# Half_Bridge.net
KiCad netlist of a schematic drawn in Altium Designer
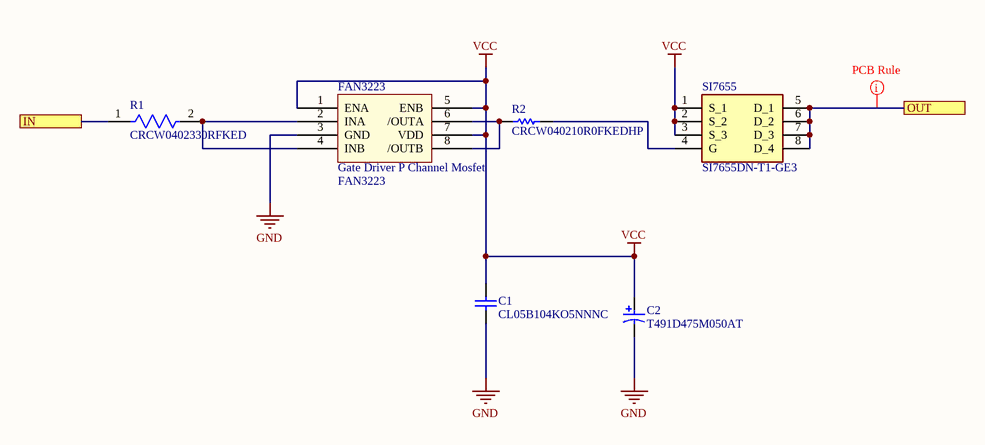
[diagram p0: Half_Bridge.SchDoc]

(export (version "E")
  (design (tool "Eeschema 10.0.6"))
  (components
    (comp (ref "C1")
      (value "CL05B104KO5NNNC")
      (footprint "CAPC1050X55X23ML05T13")
      (description "Chip Capacitor, 100 nF, +/- 10%, 16 V, -55 to 125 degC, 0402 (1005 Metric), RoHS, Tape and Reel")
      (fields (field (name "MANUFACTURER") "Samsung Electro-Mechanics"))
      (libsource (lib "Altium Content Vault") (part "CAP-NP-2"))
    )
    (comp (ref "C2")
      (value "T491D475M050AT")
      (footprint "KEMT-T491-D_L")
      (fields (field (name "VOLTAGE") "50VDC") (field (name "MANUFACTURER") "Kemet"))
      (libsource (lib "Altium Content Vault") (part "CAP-P-2"))
    )
    (comp (ref "FAN3223")
      (value "Gate Driver P Channel Mosfet")
      (footprint "FAN3223")
      (fields (field (name "ALTIUM_VALUE") "FAN3223"))
      (libsource (lib "FAN3223CMX") (part "FAN3223"))
    )
    (comp (ref "R1")
      (value "CRCW0402330RFKED")
      (footprint "FP-CRCW0402-e3-MFG")
      (description "RES Thick Film, 330Ω, 1%, 0.063W, 100ppm/°C, 0402")
      (fields (field (name "TOLERANCE") "1%"))
      (libsource (lib "Altium Content Vault") (part "1029c3af85768c4190bb7ad29bc67b5"))
    )
    (comp (ref "R2")
      (value "CRCW040210R0FKEDHP")
      (footprint "RESC1005X40X25NL05T10")
      (fields (field (name "MANUFACTURER") "Vishay Dale"))
      (libsource (lib "Altium Content Vault") (part "RES"))
    )
    (comp (ref "SI7655")
      (value "SI7655DN-T1-GE3")
      (footprint "SamacSys:SIS862DNT1GE3")
      (description "MOSFET (P-Channel)")
      (fields (field (name "MOUSER PART NUMBER") "78-SI7655DN-T1-GE3"))
      (libsource (lib "*") (part "SI7655DN-T1-GE3"))
    )
  )
  (nets
    (net (code "1") (name "/IN") (class "Default")
      (node (ref "R1") (pin "1") (pinfunction "1_1") (pintype "passive"))
    )
    (net (code "2") (name "/OUT") (class "Default")
      (node (ref "SI7655") (pin "5") (pinfunction "D_1_5") (pintype "passive"))
      (node (ref "SI7655") (pin "6") (pinfunction "D_2_6") (pintype "passive"))
      (node (ref "SI7655") (pin "7") (pinfunction "D_3_7") (pintype "passive"))
      (node (ref "SI7655") (pin "8") (pinfunction "D_4_8") (pintype "passive"))
    )
    (net (code "3") (name "GND") (class "Default")
      (node (ref "C1") (pin "1") (pinfunction "1_1") (pintype "passive"))
      (node (ref "C2") (pin "2") (pinfunction "2_2") (pintype "passive"))
      (node (ref "FAN3223") (pin "3") (pinfunction "GND_3") (pintype "passive"))
    )
    (net (code "4") (name "Net-(FAN3223-INA)") (class "Default")
      (node (ref "FAN3223") (pin "2") (pinfunction "INA_2") (pintype "passive"))
      (node (ref "FAN3223") (pin "4") (pinfunction "INB_4") (pintype "passive"))
      (node (ref "R1") (pin "2") (pinfunction "2_2") (pintype "passive"))
    )
    (net (code "5") (name "Net-(FAN3223-{slash}OUTA)") (class "Default")
      (node (ref "FAN3223") (pin "6") (pinfunction "/OUTA_6") (pintype "passive"))
      (node (ref "FAN3223") (pin "8") (pinfunction "/OUTB_8") (pintype "passive"))
      (node (ref "R2") (pin "1") (pinfunction "1_1") (pintype "passive"))
    )
    (net (code "6") (name "Net-(SI7655-G)") (class "Default")
      (node (ref "R2") (pin "2") (pinfunction "2_2") (pintype "passive"))
      (node (ref "SI7655") (pin "4") (pinfunction "G_4") (pintype "passive"))
    )
    (net (code "7") (name "VCC") (class "Default")
      (node (ref "C1") (pin "2") (pinfunction "2_2") (pintype "passive"))
      (node (ref "C2") (pin "1") (pinfunction "1_1") (pintype "passive"))
      (node (ref "FAN3223") (pin "1") (pinfunction "ENA_1") (pintype "passive"))
      (node (ref "FAN3223") (pin "5") (pinfunction "ENB_5") (pintype "passive"))
      (node (ref "FAN3223") (pin "7") (pinfunction "VDD_7") (pintype "passive"))
      (node (ref "SI7655") (pin "1") (pinfunction "S_1_1") (pintype "passive"))
      (node (ref "SI7655") (pin "2") (pinfunction "S_2_2") (pintype "passive"))
      (node (ref "SI7655") (pin "3") (pinfunction "S_3_3") (pintype "passive"))
    )
  )
)
